# ngc-breakout.net
KiCad netlist of a schematic drawn in EAGLE
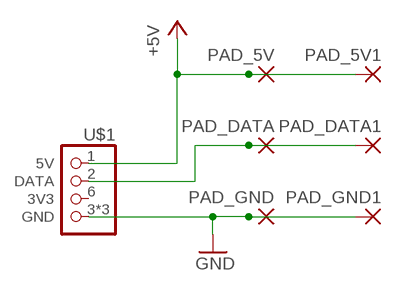
[diagram p0: schematic, sheet 1]

(export (version "E")
  (design (tool "Eeschema 10.0.6"))
  (components
    (comp (ref "PAD_5V")
      (value "SMD2")
      (footprint "eagle-import:SMD1,27-2,54")
      (libsource (lib "eagle-import") (part "SMD2"))
    )
    (comp (ref "PAD_5V1")
      (value "SMD2")
      (footprint "eagle-import:SMD1,27-2,54")
      (libsource (lib "eagle-import") (part "SMD2"))
    )
    (comp (ref "PAD_DATA")
      (value "SMD2")
      (footprint "eagle-import:SMD1,27-2,54")
      (libsource (lib "eagle-import") (part "SMD2"))
    )
    (comp (ref "PAD_DATA1")
      (value "SMD2")
      (footprint "eagle-import:SMD1,27-2,54")
      (libsource (lib "eagle-import") (part "SMD2"))
    )
    (comp (ref "PAD_GND")
      (value "SMD2")
      (footprint "eagle-import:SMD1,27-2,54")
      (libsource (lib "eagle-import") (part "SMD2"))
    )
    (comp (ref "PAD_GND1")
      (value "SMD2")
      (footprint "eagle-import:SMD1,27-2,54")
      (libsource (lib "eagle-import") (part "SMD2"))
    )
    (comp (ref "U$1")
      (value "NGC-CONNECTORGC-CONN2")
      (footprint "eagle-import:NGC-CONNECTOR")
      (libsource (lib "eagle-import") (part "NGC-CONNECTORGC-CONN2"))
    )
  )
  (nets
    (net (code "1") (name "+5V") (class "Default")
      (node (ref "PAD_5V") (pin "1") (pinfunction "P_1") (pintype "passive"))
      (node (ref "PAD_5V1") (pin "1") (pinfunction "P_1") (pintype "passive"))
      (node (ref "U$1") (pin "1") (pinfunction "5V_1") (pintype "passive"))
    )
    (net (code "2") (name "GND") (class "Default")
      (node (ref "PAD_GND") (pin "1") (pinfunction "P_1") (pintype "passive"))
      (node (ref "PAD_GND1") (pin "1") (pinfunction "P_1") (pintype "passive"))
      (node (ref "U$1") (pin "3") (pinfunction "GND_3") (pintype "passive"))
      (node (ref "U$1") (pin "4") (pinfunction "GND_4") (pintype "passive"))
      (node (ref "U$1") (pin "7") (pinfunction "GND_7") (pintype "passive"))
    )
    (net (code "3") (name "Net-(PAD_DATA-P)") (class "Default")
      (node (ref "PAD_DATA") (pin "1") (pinfunction "P_1") (pintype "passive"))
      (node (ref "PAD_DATA1") (pin "1") (pinfunction "P_1") (pintype "passive"))
      (node (ref "U$1") (pin "2") (pinfunction "DATA_2") (pintype "passive"))
    )
    (net (code "4") (name "unconnected-(U$1-3V3-Pad6)") (class "Default")
      (node (ref "U$1") (pin "6") (pinfunction "3V3_6") (pintype "passive"))
    )
  )
)
